# ESP82_Sensor_interface.net
KiCad netlist of a schematic drawn in EAGLE
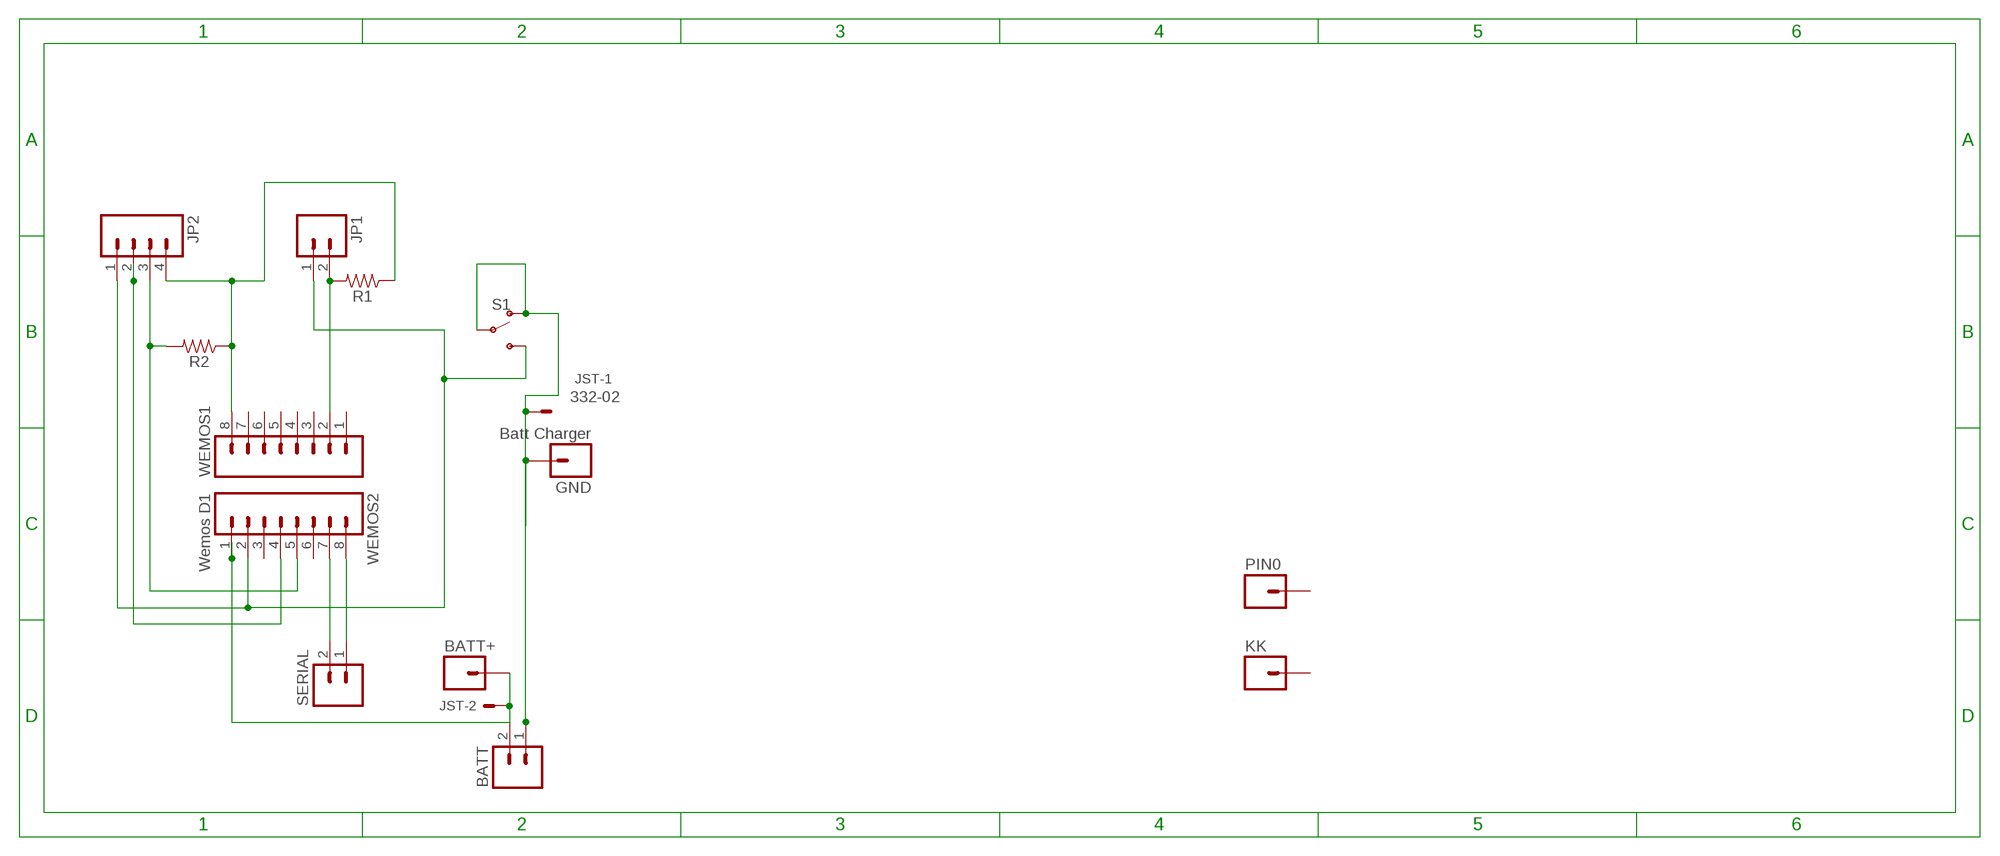
[diagram p0: schematic, sheet 1]

(export (version "E")
  (design (tool "Eeschema 10.0.6"))
  (components
    (comp (ref "BATT")
      (value "M02LOCK_LONGPADS")
      (footprint "eagle-import:1X02_LOCK_LONGPADS")
      (libsource (lib "eagle-import") (part "M02LOCK_LONGPADS"))
    )
    (comp (ref "BATT+")
      (value "M01PTH")
      (footprint "eagle-import:1X01")
      (libsource (lib "eagle-import") (part "M01PTH"))
    )
    (comp (ref "GND")
      (value "Batt Charger")
      (footprint "eagle-import:1X01")
      (libsource (lib "eagle-import") (part "M01PTH"))
    )
    (comp (ref "JP1")
      (value "M02PTH")
      (footprint "eagle-import:1X02")
      (libsource (lib "eagle-import") (part "SparkFun-Connectors_6242394_M02PTH"))
    )
    (comp (ref "JP2")
      (value "M04PTH")
      (footprint "eagle-import:1X04")
      (libsource (lib "eagle-import") (part "M04PTH"))
    )
    (comp (ref "JST")
      (value "332-02")
      (footprint "eagle-import:332-02")
      (libsource (lib "eagle-import") (part "332-02"))
    )
    (comp (ref "KK")
      (value "M01PTH")
      (footprint "eagle-import:1X01")
      (libsource (lib "eagle-import") (part "M01PTH"))
    )
    (comp (ref "PIN0")
      (value "M01PTH")
      (footprint "eagle-import:1X01")
      (libsource (lib "eagle-import") (part "M01PTH"))
    )
    (comp (ref "R1")
      (value "RESISTOR1206")
      (footprint "eagle-import:1206")
      (libsource (lib "eagle-import") (part "RESISTOR1206"))
    )
    (comp (ref "R2")
      (value "RESISTOR1206")
      (footprint "eagle-import:1206")
      (libsource (lib "eagle-import") (part "RESISTOR1206"))
    )
    (comp (ref "S1")
      (value "SWITCH-SPDT-SMD-RIGHT-ANGLE")
      (footprint "eagle-import:SWITCH_SPST_SMD_A")
      (libsource (lib "eagle-import") (part "SWITCH-SPDT-SMD-RIGHT-ANGLE"))
    )
    (comp (ref "SERIAL")
      (value "M02PTH")
      (footprint "eagle-import:1X02")
      (libsource (lib "eagle-import") (part "SparkFun-Connectors_6242394_M02PTH"))
    )
    (comp (ref "WEMOS1")
      (value "M08")
      (footprint "eagle-import:1X08_ROUND")
      (libsource (lib "eagle-import") (part "M08"))
    )
    (comp (ref "WEMOS2")
      (value "Wemos D1")
      (footprint "eagle-import:1X08_ROUND")
      (libsource (lib "eagle-import") (part "M08"))
    )
  )
  (nets
    (net (code "1") (name "Net-(JP1-Pad2)") (class "Default")
      (node (ref "JP1") (pin "2") (pinfunction "2_2") (pintype "passive"))
      (node (ref "R1") (pin "2") (pinfunction "2_2") (pintype "passive"))
      (node (ref "WEMOS1") (pin "2") (pinfunction "2_2") (pintype "passive"))
    )
    (net (code "2") (name "Net-(JP2-Pad2)") (class "Default")
      (node (ref "JP2") (pin "2") (pinfunction "2_2") (pintype "passive"))
      (node (ref "WEMOS2") (pin "4") (pinfunction "4_4") (pintype "passive"))
    )
    (net (code "3") (name "Net-(JP2-Pad3)") (class "Default")
      (node (ref "JP2") (pin "3") (pinfunction "3_3") (pintype "passive"))
      (node (ref "R2") (pin "2") (pinfunction "2_2") (pintype "passive"))
      (node (ref "WEMOS2") (pin "5") (pinfunction "5_5") (pintype "passive"))
    )
    (net (code "4") (name "Net-(JP2-Pad4)") (class "Default")
      (node (ref "JP2") (pin "4") (pinfunction "4_4") (pintype "passive"))
      (node (ref "R1") (pin "1") (pinfunction "1_1") (pintype "passive"))
      (node (ref "R2") (pin "1") (pinfunction "1_1") (pintype "passive"))
      (node (ref "WEMOS1") (pin "8") (pinfunction "8_8") (pintype "passive"))
    )
    (net (code "5") (name "Net-(JSTA-S)") (class "Default")
      (node (ref "BATT") (pin "1") (pinfunction "1_1") (pintype "passive"))
      (node (ref "GND") (pin "1") (pinfunction "1_1") (pintype "passive"))
      (node (ref "JST") (pin "1") (pinfunction "S_1") (pintype "passive"))
      (node (ref "S1") (pin "1") (pinfunction "O_1") (pintype "passive"))
      (node (ref "S1") (pin "2") (pinfunction "P_2") (pintype "passive"))
    )
    (net (code "6") (name "Net-(JSTB-S)") (class "Default")
      (node (ref "BATT") (pin "2") (pinfunction "2_2") (pintype "passive"))
      (node (ref "BATT+") (pin "1") (pinfunction "1_1") (pintype "passive"))
      (node (ref "JST") (pin "2") (pinfunction "S_2") (pintype "passive"))
      (node (ref "WEMOS2") (pin "1") (pinfunction "1_1") (pintype "passive"))
    )
    (net (code "7") (name "Net-(S1-S)") (class "Default")
      (node (ref "JP1") (pin "1") (pinfunction "1_1") (pintype "passive"))
      (node (ref "JP2") (pin "1") (pinfunction "1_1") (pintype "passive"))
      (node (ref "S1") (pin "3") (pinfunction "S_3") (pintype "passive"))
      (node (ref "WEMOS2") (pin "2") (pinfunction "2_2") (pintype "passive"))
    )
    (net (code "8") (name "Net-(SERIAL-Pad1)") (class "Default")
      (node (ref "SERIAL") (pin "1") (pinfunction "1_1") (pintype "passive"))
      (node (ref "WEMOS2") (pin "8") (pinfunction "8_8") (pintype "passive"))
    )
    (net (code "9") (name "Net-(SERIAL-Pad2)") (class "Default")
      (node (ref "SERIAL") (pin "2") (pinfunction "2_2") (pintype "passive"))
      (node (ref "WEMOS2") (pin "7") (pinfunction "7_7") (pintype "passive"))
    )
    (net (code "10") (name "unconnected-(KK-Pad1)") (class "Default")
      (node (ref "KK") (pin "1") (pinfunction "1_1") (pintype "passive"))
    )
    (net (code "11") (name "unconnected-(PIN0-Pad1)") (class "Default")
      (node (ref "PIN0") (pin "1") (pinfunction "1_1") (pintype "passive"))
    )
    (net (code "12") (name "unconnected-(WEMOS1-Pad1)") (class "Default")
      (node (ref "WEMOS1") (pin "1") (pinfunction "1_1") (pintype "passive"))
    )
    (net (code "13") (name "unconnected-(WEMOS1-Pad3)") (class "Default")
      (node (ref "WEMOS1") (pin "3") (pinfunction "3_3") (pintype "passive"))
    )
    (net (code "14") (name "unconnected-(WEMOS1-Pad4)") (class "Default")
      (node (ref "WEMOS1") (pin "4") (pinfunction "4_4") (pintype "passive"))
    )
    (net (code "15") (name "unconnected-(WEMOS1-Pad5)") (class "Default")
      (node (ref "WEMOS1") (pin "5") (pinfunction "5_5") (pintype "passive"))
    )
    (net (code "16") (name "unconnected-(WEMOS1-Pad6)") (class "Default")
      (node (ref "WEMOS1") (pin "6") (pinfunction "6_6") (pintype "passive"))
    )
    (net (code "17") (name "unconnected-(WEMOS1-Pad7)") (class "Default")
      (node (ref "WEMOS1") (pin "7") (pinfunction "7_7") (pintype "passive"))
    )
    (net (code "18") (name "unconnected-(WEMOS2-Pad3)") (class "Default")
      (node (ref "WEMOS2") (pin "3") (pinfunction "3_3") (pintype "passive"))
    )
    (net (code "19") (name "unconnected-(WEMOS2-Pad6)") (class "Default")
      (node (ref "WEMOS2") (pin "6") (pinfunction "6_6") (pintype "passive"))
    )
  )
)
